# CSI2-NITROGEN_Rev01.net
KiCad netlist of a schematic drawn in Altium Designer
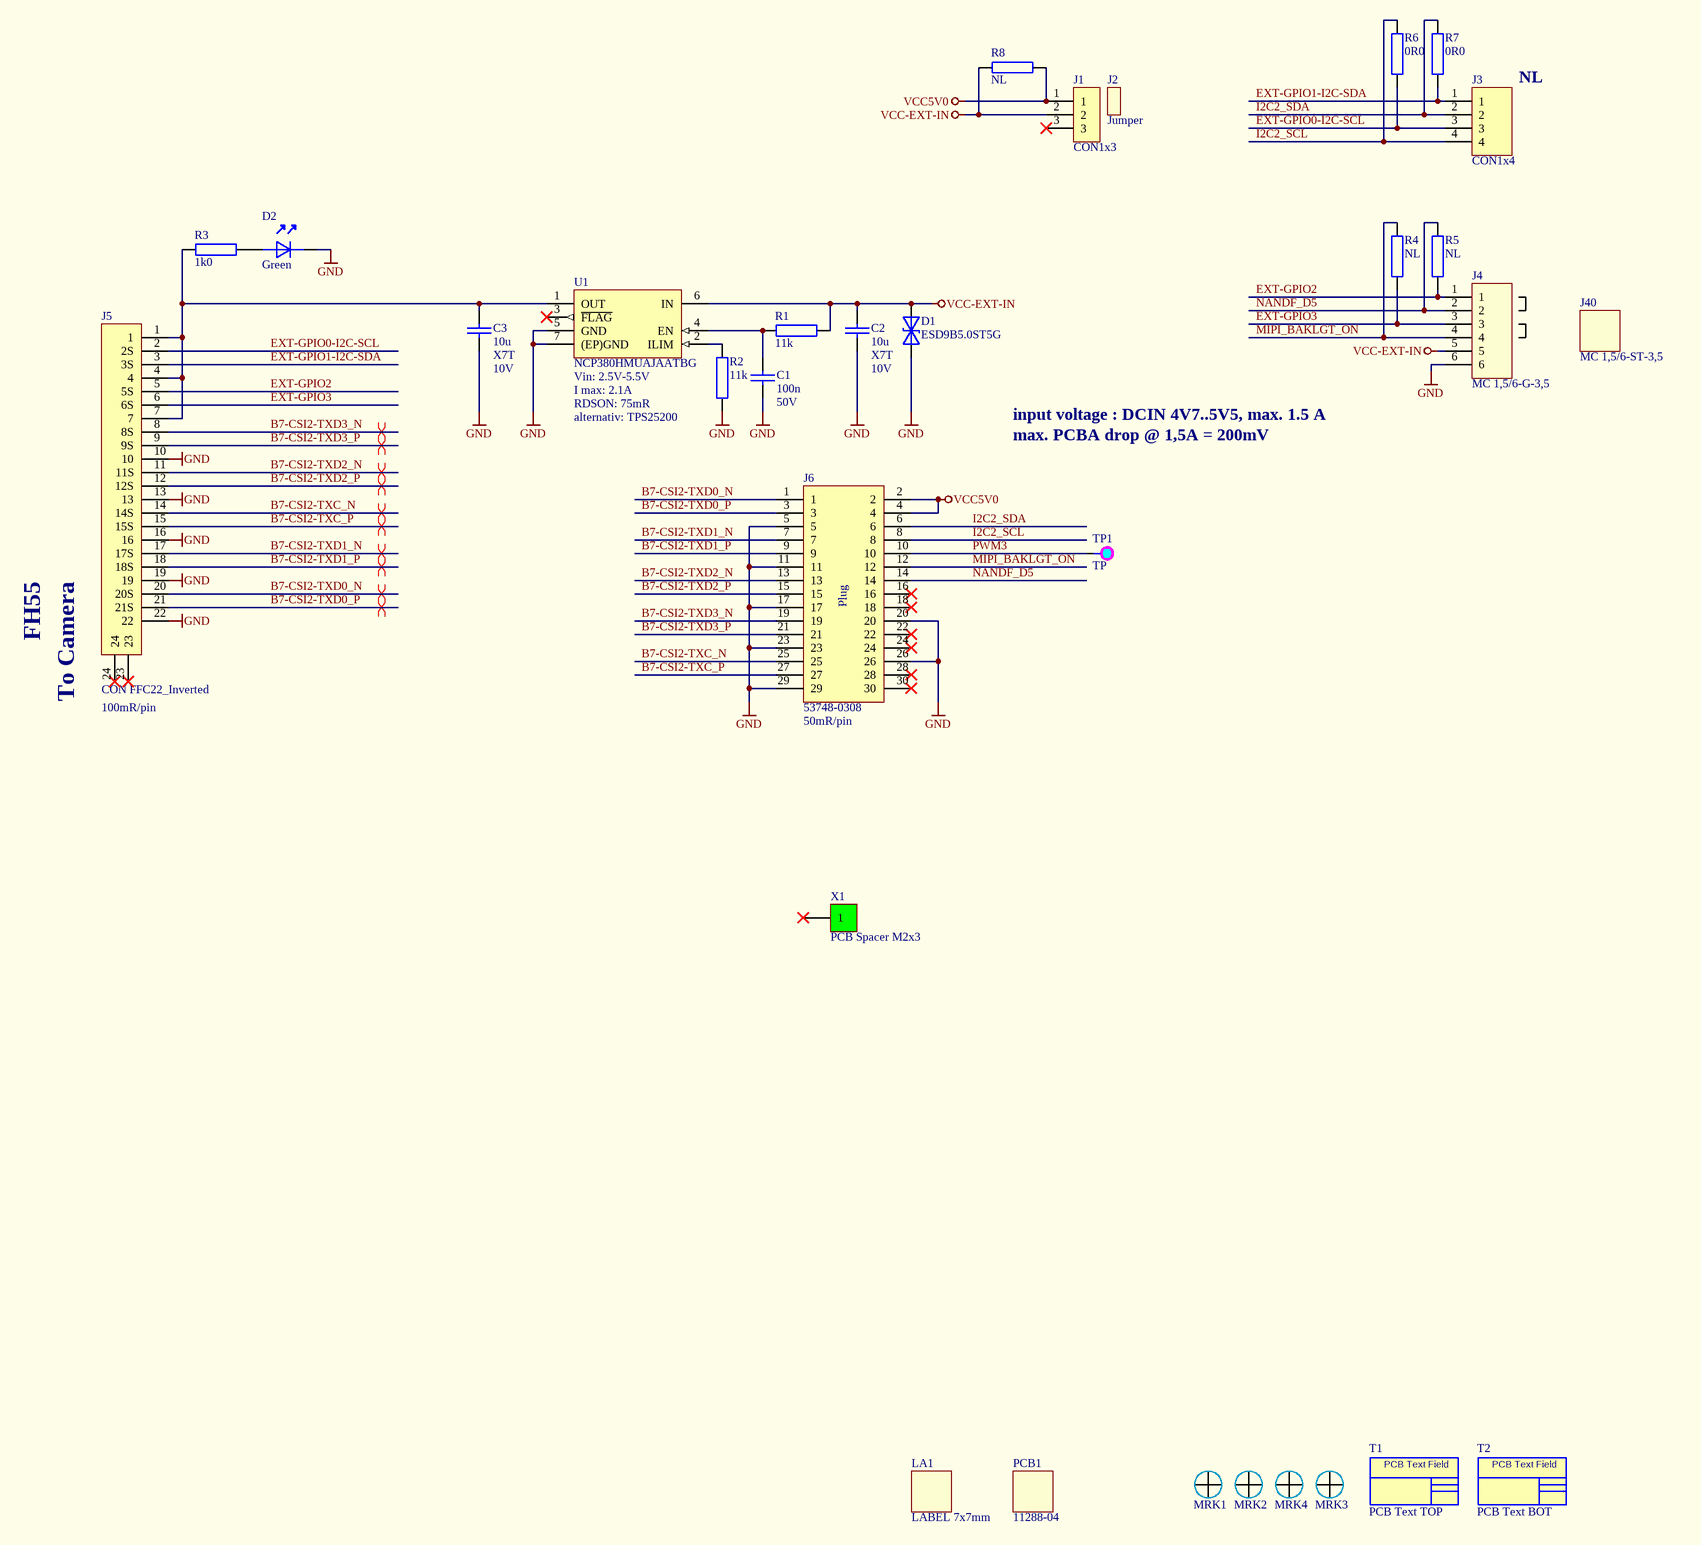
[diagram p0: CSI2-NITROGEN_Rev01.SchDoc]

(export (version "E")
  (design (tool "Eeschema 10.0.6"))
  (components
    (comp (ref "C1")
      (value "100n")
      (footprint "C-0603_1.0")
      (description "Capacitor Ceramic SMD/0603/50V/X7R/10%")
      (fields
        (field (name "KHK PART NUMBER") "K8340023")
        (field (name "MANUFACTURER") "several")
        (field (name "VOLTAGE") "50V")
      )
      (libsource (lib "AVT_KHK_Lib") (part "C 100N 50V X7R 0603"))
    )
    (comp (ref "C2")
      (value "10u")
      (footprint "C-0603_1.0")
      (description "Capacitor Ceramic SMD/0603/10V/X7T/20%/125°C")
      (fields
        (field (name "KHK PART NUMBER") "10509")
        (field (name "MANUFACTURER") "several")
        (field (name "DIELECTRIC") "X7T")
        (field (name "VOLTAGE") "10V")
      )
      (libsource (lib "AVT_KHK_Lib") (part "C 10U 10V X7T 0603 125°C"))
    )
    (comp (ref "C3")
      (value "10u")
      (footprint "C-0603_1.0")
      (description "Capacitor Ceramic SMD/0603/10V/X7T/20%/125°C")
      (fields
        (field (name "KHK PART NUMBER") "10509")
        (field (name "MANUFACTURER") "several")
        (field (name "DIELECTRIC") "X7T")
        (field (name "VOLTAGE") "10V")
      )
      (libsource (lib "AVT_KHK_Lib") (part "C 10U 10V X7T 0603 125°C"))
    )
    (comp (ref "D1")
      (value "ESD9B5.0ST5G")
      (footprint "D-SOD923")
      (description "DIODE TVS; 400W; 5.8-7.8V; BIDIRECT")
      (fields (field (name "KHK PART NUMBER") "7250") (field (name "MANUFACTURER") "ON Semiconductor"))
      (libsource (lib "AVT_KHK_Lib") (part "D ESD9B5.0ST5G"))
    )
    (comp (ref "D2")
      (value "Green")
      (footprint "D-0603-SLED")
      (description "Side LED 0603 20mA green")
      (fields (field (name "KHK PART NUMBER") "4248") (field (name "MANUFACTURER") "several"))
      (libsource (lib "AVT_KHK_Lib") (part "D Side LED 0603 green"))
    )
    (comp (ref "J1")
      (value "CON1x3")
      (footprint "CON 1x3 RM2.54")
      (description "Stiftleiste; 1x3; 2.54mm; gerade")
      (fields
        (field (name "MANUFACTURER") "fischer elektronik")
        (field (name "MANUFACTURER PART NUMBER") "SL 11 124 3 G")
      )
      (libsource (lib "AVT_KHK_Lib") (part "CON 1x3 2.54"))
    )
    (comp (ref "J2")
      (value "Jumper")
      (footprint "J-JUMPER-2.54")
      (description "CON/JUMPER/STC02SYAN; 2-pin; 2.54mm; 3A; FEMALE; VERTICAL; BLACK")
      (fields (field (name "KHK PART NUMBER") "13444") (field (name "MANUFACTURER") "several"))
      (libsource (lib "AVT_KHK_Lib") (part "CON Jumper 2.54mm"))
    )
    (comp (ref "J3")
      (value "CON1x4")
      (footprint "CON 1x4 RM2.54")
      (description "Stiftleiste; 1x4; 2.54mm; gerade")
      (fields (field (name "MANUFACTURER") "Harwin") (field (name "MANUFACTURER PART NUMBER") "M20-999 0445"))
      (libsource (lib "AVT_KHK_Lib") (part "CON 1x4 2.54"))
    )
    (comp (ref "J4")
      (value "MC 1,5/6-G-3,5")
      (footprint "CON_MiniCon 6pol 3mm5")
      (description "Phoenix MC 1,5/6-G-3,5 MiniCon 6polig 3,5mm")
      (fields (field (name "KHK PART NUMBER") "K7600569") (field (name "MANUFACTURER") "Phoenix"))
      (libsource (lib "AVT_KHK_Lib") (part "CON MiniCon 6pol 3mm5"))
    )
    (comp (ref "J5")
      (value "CON FFC22_Inverted")
      (footprint "J-FH55-22S-0.5SH - Inverted Pins")
      (description "FFC Connector 0.5mm shielded")
      (fields
        (field (name "KHK PART NUMBER") "10357")
        (field (name "MANUFACTURER PART NUMBER") "FH55-22S-0.5SH")
      )
      (libsource (lib "AVT_KHK_Lib") (part "CON FFC22_FH55-22S-0.5SH_Inverted"))
    )
    (comp (ref "J6")
      (value "53748-0308")
      (footprint "J-MOLEX-53748-0308")
      (description "30pin B2B plug 0.5 pitch 3mm Height")
      (fields (field (name "MANUFACTURER") "Molex") (field (name "KHK PART NUMBER") "10287"))
      (libsource (lib "AVT_KHK_Lib") (part "CON Molex 53748-0308"))
    )
    (comp (ref "J40")
      (value "MC 1,5/6-ST-3,5")
      (description "Phoenix MC 1,5/6-ST-3,5 MiniCon 6polig 3,5mm")
      (fields (field (name "KHK PART NUMBER") "1818") (field (name "MANUFACTURER") "Phoenix"))
      (libsource (lib "AVT_KHK_Lib") (part "CON MiniCon 6pol 3mm5 ST"))
    )
    (comp (ref "LA1")
      (value "LABEL 7x7mm")
      (footprint "PCB LABEL 7x7")
      (fields (field (name "MANUFACTURER") "several"))
      (libsource (lib "AVT_KHK_Lib") (part "PCB LABEL 7x7"))
    )
    (comp (ref "MRK1")
      (value "Marker Single Layer")
      (footprint "PCB_Marker_Pad_top")
      (description "Position Marker for PCBs")
      (libsource (lib "AVT_KHK_Lib") (part "PCB Marker Pad Single Layer"))
    )
    (comp (ref "MRK2")
      (value "Marker Single Layer")
      (footprint "PCB_Marker_Pad_top")
      (description "Position Marker for PCBs")
      (libsource (lib "AVT_KHK_Lib") (part "PCB Marker Pad Single Layer"))
    )
    (comp (ref "MRK3")
      (value "Marker Single Layer")
      (footprint "PCB_Marker_Pad_top")
      (description "Position Marker for PCBs")
      (libsource (lib "AVT_KHK_Lib") (part "PCB Marker Pad Single Layer"))
    )
    (comp (ref "MRK4")
      (value "Marker Single Layer")
      (footprint "PCB_Marker_Pad_top")
      (description "Position Marker for PCBs")
      (libsource (lib "AVT_KHK_Lib") (part "PCB Marker Pad Single Layer"))
    )
    (comp (ref "PCB1")
      (value "11288-04")
      (description "PCB ML04")
      (fields (field (name "MANUFACTURER") "several"))
      (libsource (lib "AVT_KHK_Lib") (part "PCB"))
    )
    (comp (ref "R1")
      (value "11k")
      (footprint "R-0603_0.6")
      (description "Standard Resistor SMD/0603/1%/100mW/TK100")
      (fields (field (name "KHK PART NUMBER") "K8250147") (field (name "MANUFACTURER") "several"))
      (libsource (lib "AVT_KHK_Lib") (part "R 11K 1% 0603"))
    )
    (comp (ref "R2")
      (value "11k")
      (footprint "R-0603_0.6")
      (description "Standard Resistor SMD/0603/1%/100mW/TK100")
      (fields (field (name "KHK PART NUMBER") "K8250147") (field (name "MANUFACTURER") "several"))
      (libsource (lib "AVT_KHK_Lib") (part "R 11K 1% 0603"))
    )
    (comp (ref "R3")
      (value "1k0")
      (footprint "R-0603_0.6")
      (description "Standard Resistor SMD/0603/1%/100mW/TK100")
      (fields (field (name "KHK PART NUMBER") "K8250040") (field (name "MANUFACTURER") "several"))
      (libsource (lib "AVT_KHK_Lib") (part "R 1K0 1% 0603"))
    )
    (comp (ref "R4")
      (value "NL")
      (footprint "R-0603_0.6")
      (description "Standard Resistor SMD/0603/1%/100mW/TK100")
      (fields (field (name "TOLERANCE") "1%"))
      (libsource (lib "AVT_KHK_Lib") (part "R X 0603"))
    )
    (comp (ref "R5")
      (value "NL")
      (footprint "R-0603_0.6")
      (description "Standard Resistor SMD/0603/1%/100mW/TK100")
      (fields (field (name "TOLERANCE") "1%"))
      (libsource (lib "AVT_KHK_Lib") (part "R X 0603"))
    )
    (comp (ref "R6")
      (value "0R0")
      (footprint "R-0603_0.6")
      (description "Standard Resistor SMD/0603/1%/100mW/TK100")
      (fields (field (name "KHK PART NUMBER") "K8250041") (field (name "MANUFACTURER") "several"))
      (libsource (lib "AVT_KHK_Lib") (part "R 0R0 1% 0603"))
    )
    (comp (ref "R7")
      (value "0R0")
      (footprint "R-0603_0.6")
      (description "Standard Resistor SMD/0603/1%/100mW/TK100")
      (fields (field (name "KHK PART NUMBER") "K8250041") (field (name "MANUFACTURER") "several"))
      (libsource (lib "AVT_KHK_Lib") (part "R 0R0 1% 0603"))
    )
    (comp (ref "R8")
      (value "NL")
      (footprint "R-0603_0.6")
      (description "Standard Resistor SMD/0603/1%/100mW/TK100")
      (fields (field (name "TOLERANCE") "1%"))
      (libsource (lib "AVT_KHK_Lib") (part "R X 0603"))
    )
    (comp (ref "T1")
      (value "PCB Text TOP")
      (footprint "PCB TEXTFIELD TOP 2")
      (description "PCB Textfield TOP")
      (libsource (lib "AVT_KHK_Lib") (part "PCB TEXT FIELD TOP"))
    )
    (comp (ref "T2")
      (value "PCB Text BOT")
      (footprint "PCB TEXTFIELD BOT 2")
      (description "PCB Textfield BOT")
      (libsource (lib "AVT_KHK_Lib") (part "PCB TEXT FIELD BOT"))
    )
    (comp (ref "TP1")
      (value "TP")
      (footprint "TP_11_065")
      (description "Testpoint: Pad=1,1mm; Hole=0,65mm")
      (libsource (lib "AVT_KHK_Lib") (part "TP_11_065"))
    )
    (comp (ref "U1")
      (value "NCP380HMUAJAATBG")
      (footprint "IC-DFN06_2.0x2.0x0.8")
      (description "IC/PWR/LOADSW;1V2-5V5;3A;0R03/WLCSP6/1x1.5x0.63mm")
      (fields
        (field (name "KHK PART NUMBER") "13676")
        (field (name "MANUFACTURER") "onsemi")
        (field (name "VIN") "2.5V-5.5V")
        (field (name "I MAX") "2.1A")
      )
      (libsource (lib "AVT_KHK_Lib") (part "IC  NCP380HMUAJAATBG"))
    )
    (comp (ref "X1")
      (value "PCB Spacer M2x3")
      (footprint "X-HOLE-2.9-4.0-DK_AH_3.0")
      (description "Abstandsbuchse SMTSO-2,1-3 ET")
      (fields (field (name "MANUFACTURER") "KVT") (field (name "MANUFACTURER PART NUMBER") "SMTSO-2,1-3 ET"))
      (libsource (lib "AVT_KHK_Lib") (part "PCB Spacer M2x3"))
    )
  )
  (nets
    (net (code "1") (name "/B7-CSI2-TXC_N") (class "Default")
      (node (ref "J5") (pin "14") (pinfunction "14S_14") (pintype "passive"))
      (node (ref "J6") (pin "25") (pinfunction "25_25") (pintype "passive"))
    )
    (net (code "2") (name "/B7-CSI2-TXC_P") (class "Default")
      (node (ref "J5") (pin "15") (pinfunction "15S_15") (pintype "passive"))
      (node (ref "J6") (pin "27") (pinfunction "27_27") (pintype "passive"))
    )
    (net (code "3") (name "/B7-CSI2-TXD0_N") (class "Default")
      (node (ref "J5") (pin "20") (pinfunction "20S_20") (pintype "passive"))
      (node (ref "J6") (pin "1") (pinfunction "1_1") (pintype "passive"))
    )
    (net (code "4") (name "/B7-CSI2-TXD0_P") (class "Default")
      (node (ref "J5") (pin "21") (pinfunction "21S_21") (pintype "passive"))
      (node (ref "J6") (pin "3") (pinfunction "3_3") (pintype "passive"))
    )
    (net (code "5") (name "/B7-CSI2-TXD1_N") (class "Default")
      (node (ref "J5") (pin "17") (pinfunction "17S_17") (pintype "passive"))
      (node (ref "J6") (pin "7") (pinfunction "7_7") (pintype "passive"))
    )
    (net (code "6") (name "/B7-CSI2-TXD1_P") (class "Default")
      (node (ref "J5") (pin "18") (pinfunction "18S_18") (pintype "passive"))
      (node (ref "J6") (pin "9") (pinfunction "9_9") (pintype "passive"))
    )
    (net (code "7") (name "/B7-CSI2-TXD2_N") (class "Default")
      (node (ref "J5") (pin "11") (pinfunction "11S_11") (pintype "passive"))
      (node (ref "J6") (pin "13") (pinfunction "13_13") (pintype "passive"))
    )
    (net (code "8") (name "/B7-CSI2-TXD2_P") (class "Default")
      (node (ref "J5") (pin "12") (pinfunction "12S_12") (pintype "passive"))
      (node (ref "J6") (pin "15") (pinfunction "15_15") (pintype "passive"))
    )
    (net (code "9") (name "/B7-CSI2-TXD3_N") (class "Default")
      (node (ref "J5") (pin "8") (pinfunction "8S_8") (pintype "passive"))
      (node (ref "J6") (pin "19") (pinfunction "19_19") (pintype "passive"))
    )
    (net (code "10") (name "/B7-CSI2-TXD3_P") (class "Default")
      (node (ref "J5") (pin "9") (pinfunction "9S_9") (pintype "passive"))
      (node (ref "J6") (pin "21") (pinfunction "21_21") (pintype "passive"))
    )
    (net (code "11") (name "/EXT-GPIO0-I2C-SCL") (class "Default")
      (node (ref "J3") (pin "3") (pinfunction "3_3") (pintype "passive"))
      (node (ref "J5") (pin "2") (pinfunction "2S_2") (pintype "passive"))
      (node (ref "R6") (pin "1") (pinfunction "1_1") (pintype "passive"))
    )
    (net (code "12") (name "/EXT-GPIO1-I2C-SDA") (class "Default")
      (node (ref "J3") (pin "1") (pinfunction "1_1") (pintype "passive"))
      (node (ref "J5") (pin "3") (pinfunction "3S_3") (pintype "passive"))
      (node (ref "R7") (pin "1") (pinfunction "1_1") (pintype "passive"))
    )
    (net (code "13") (name "/EXT-GPIO2") (class "Default")
      (node (ref "J4") (pin "1") (pinfunction "1_1") (pintype "passive"))
      (node (ref "J5") (pin "5") (pinfunction "5S_5") (pintype "passive"))
      (node (ref "R5") (pin "1") (pinfunction "1_1") (pintype "passive"))
    )
    (net (code "14") (name "/EXT-GPIO3") (class "Default")
      (node (ref "J4") (pin "3") (pinfunction "3_3") (pintype "passive"))
      (node (ref "J5") (pin "6") (pinfunction "6S_6") (pintype "passive"))
      (node (ref "R4") (pin "1") (pinfunction "1_1") (pintype "passive"))
    )
    (net (code "15") (name "/I2C2_SCL") (class "Default")
      (node (ref "J3") (pin "4") (pinfunction "4_4") (pintype "passive"))
      (node (ref "J6") (pin "8") (pinfunction "8_8") (pintype "passive"))
      (node (ref "R6") (pin "2") (pinfunction "2_2") (pintype "passive"))
    )
    (net (code "16") (name "/I2C2_SDA") (class "Default")
      (node (ref "J3") (pin "2") (pinfunction "2_2") (pintype "passive"))
      (node (ref "J6") (pin "6") (pinfunction "6_6") (pintype "passive"))
      (node (ref "R7") (pin "2") (pinfunction "2_2") (pintype "passive"))
    )
    (net (code "17") (name "/MIPI_BAKLGT_ON") (class "Default")
      (node (ref "J4") (pin "4") (pinfunction "4_4") (pintype "passive"))
      (node (ref "J6") (pin "12") (pinfunction "12_12") (pintype "passive"))
      (node (ref "R4") (pin "2") (pinfunction "2_2") (pintype "passive"))
    )
    (net (code "18") (name "/NANDF_D5") (class "Default")
      (node (ref "J4") (pin "2") (pinfunction "2_2") (pintype "passive"))
      (node (ref "J6") (pin "14") (pinfunction "14_14") (pintype "passive"))
      (node (ref "R5") (pin "2") (pinfunction "2_2") (pintype "passive"))
    )
    (net (code "19") (name "/PWM3") (class "Default")
      (node (ref "J6") (pin "10") (pinfunction "10_10") (pintype "passive"))
      (node (ref "TP1") (pin "1") (pinfunction "1_1") (pintype "passive"))
    )
    (net (code "20") (name "GND") (class "Default")
      (node (ref "C1") (pin "2") (pinfunction "2_2") (pintype "passive"))
      (node (ref "C2") (pin "2") (pinfunction "2_2") (pintype "passive"))
      (node (ref "C3") (pin "2") (pinfunction "2_2") (pintype "passive"))
      (node (ref "D1") (pin "A") (pinfunction "A_A") (pintype "passive"))
      (node (ref "D2") (pin "K") (pinfunction "2_K") (pintype "passive"))
      (node (ref "J4") (pin "6") (pinfunction "6_6") (pintype "passive"))
      (node (ref "J5") (pin "10") (pinfunction "10_10") (pintype "passive"))
      (node (ref "J5") (pin "13") (pinfunction "13_13") (pintype "passive"))
      (node (ref "J5") (pin "16") (pinfunction "16_16") (pintype "passive"))
      (node (ref "J5") (pin "19") (pinfunction "19_19") (pintype "passive"))
      (node (ref "J5") (pin "22") (pinfunction "22_22") (pintype "passive"))
      (node (ref "J6") (pin "11") (pinfunction "11_11") (pintype "passive"))
      (node (ref "J6") (pin "17") (pinfunction "17_17") (pintype "passive"))
      (node (ref "J6") (pin "20") (pinfunction "20_20") (pintype "passive"))
      (node (ref "J6") (pin "23") (pinfunction "23_23") (pintype "passive"))
      (node (ref "J6") (pin "26") (pinfunction "26_26") (pintype "passive"))
      (node (ref "J6") (pin "29") (pinfunction "29_29") (pintype "passive"))
      (node (ref "J6") (pin "5") (pinfunction "5_5") (pintype "passive"))
      (node (ref "R2") (pin "1") (pinfunction "1_1") (pintype "passive"))
      (node (ref "U1") (pin "5") (pinfunction "GND_5") (pintype "power_in"))
      (node (ref "U1") (pin "7") (pinfunction "(EP)GND_7") (pintype "power_in"))
    )
    (net (code "21") (name "Net-(D2-1)") (class "Default")
      (node (ref "D2") (pin "A") (pinfunction "1_A") (pintype "passive"))
      (node (ref "R3") (pin "2") (pinfunction "2_2") (pintype "passive"))
    )
    (net (code "22") (name "Net-(U1-EN)") (class "Default")
      (node (ref "C1") (pin "1") (pinfunction "1_1") (pintype "passive"))
      (node (ref "R1") (pin "2") (pinfunction "2_2") (pintype "passive"))
      (node (ref "U1") (pin "4") (pinfunction "EN_4") (pintype "input"))
    )
    (net (code "23") (name "Net-(U1-ILIM)") (class "Default")
      (node (ref "R2") (pin "2") (pinfunction "2_2") (pintype "passive"))
      (node (ref "U1") (pin "2") (pinfunction "ILIM_2") (pintype "input"))
    )
    (net (code "24") (name "Net-(U1-OUT)") (class "Default")
      (node (ref "C3") (pin "1") (pinfunction "1_1") (pintype "passive"))
      (node (ref "J5") (pin "1") (pinfunction "1_1") (pintype "passive"))
      (node (ref "J5") (pin "4") (pinfunction "4_4") (pintype "passive"))
      (node (ref "J5") (pin "7") (pinfunction "7_7") (pintype "passive"))
      (node (ref "R3") (pin "1") (pinfunction "1_1") (pintype "passive"))
      (node (ref "U1") (pin "1") (pinfunction "OUT_1") (pintype "power_in"))
    )
    (net (code "25") (name "VCC-EXT-IN") (class "Default")
      (node (ref "C2") (pin "1") (pinfunction "1_1") (pintype "passive"))
      (node (ref "D1") (pin "K") (pinfunction "K_K") (pintype "passive"))
      (node (ref "J1") (pin "2") (pinfunction "2_2") (pintype "passive"))
      (node (ref "J4") (pin "5") (pinfunction "5_5") (pintype "passive"))
      (node (ref "R1") (pin "1") (pinfunction "1_1") (pintype "passive"))
      (node (ref "R8") (pin "2") (pinfunction "2_2") (pintype "passive"))
      (node (ref "U1") (pin "6") (pinfunction "IN_6") (pintype "power_in"))
    )
    (net (code "26") (name "VCC5V0") (class "Default")
      (node (ref "J1") (pin "1") (pinfunction "1_1") (pintype "passive"))
      (node (ref "J6") (pin "2") (pinfunction "2_2") (pintype "passive"))
      (node (ref "J6") (pin "4") (pinfunction "4_4") (pintype "passive"))
      (node (ref "R8") (pin "1") (pinfunction "1_1") (pintype "passive"))
    )
    (net (code "27") (name "unconnected-(J1-Pad3)") (class "Default")
      (node (ref "J1") (pin "3") (pinfunction "3_3") (pintype "passive+no_connect"))
    )
    (net (code "28") (name "unconnected-(J5-Pad23)") (class "Default")
      (node (ref "J5") (pin "23") (pinfunction "23_23") (pintype "passive+no_connect"))
    )
    (net (code "29") (name "unconnected-(J5-Pad24)") (class "Default")
      (node (ref "J5") (pin "24") (pinfunction "24_24") (pintype "passive+no_connect"))
    )
    (net (code "30") (name "unconnected-(J6-Pad16)") (class "Default")
      (node (ref "J6") (pin "16") (pinfunction "16_16") (pintype "passive+no_connect"))
    )
    (net (code "31") (name "unconnected-(J6-Pad18)") (class "Default")
      (node (ref "J6") (pin "18") (pinfunction "18_18") (pintype "passive+no_connect"))
    )
    (net (code "32") (name "unconnected-(J6-Pad22)") (class "Default")
      (node (ref "J6") (pin "22") (pinfunction "22_22") (pintype "passive+no_connect"))
    )
    (net (code "33") (name "unconnected-(J6-Pad24)") (class "Default")
      (node (ref "J6") (pin "24") (pinfunction "24_24") (pintype "passive+no_connect"))
    )
    (net (code "34") (name "unconnected-(J6-Pad28)") (class "Default")
      (node (ref "J6") (pin "28") (pinfunction "28_28") (pintype "passive+no_connect"))
    )
    (net (code "35") (name "unconnected-(J6-Pad30)") (class "Default")
      (node (ref "J6") (pin "30") (pinfunction "30_30") (pintype "passive+no_connect"))
    )
    (net (code "36") (name "unconnected-(U1-~{FLAG}-Pad3)") (class "Default")
      (node (ref "U1") (pin "3") (pinfunction "~{FLAG}_3") (pintype "output+no_connect"))
    )
    (net (code "37") (name "unconnected-(X1-Pad1)") (class "Default")
      (node (ref "X1") (pin "1") (pinfunction "1_1") (pintype "passive+no_connect"))
    )
  )
)
